# PinJoy.net
KiCad netlist of a schematic drawn in EAGLE
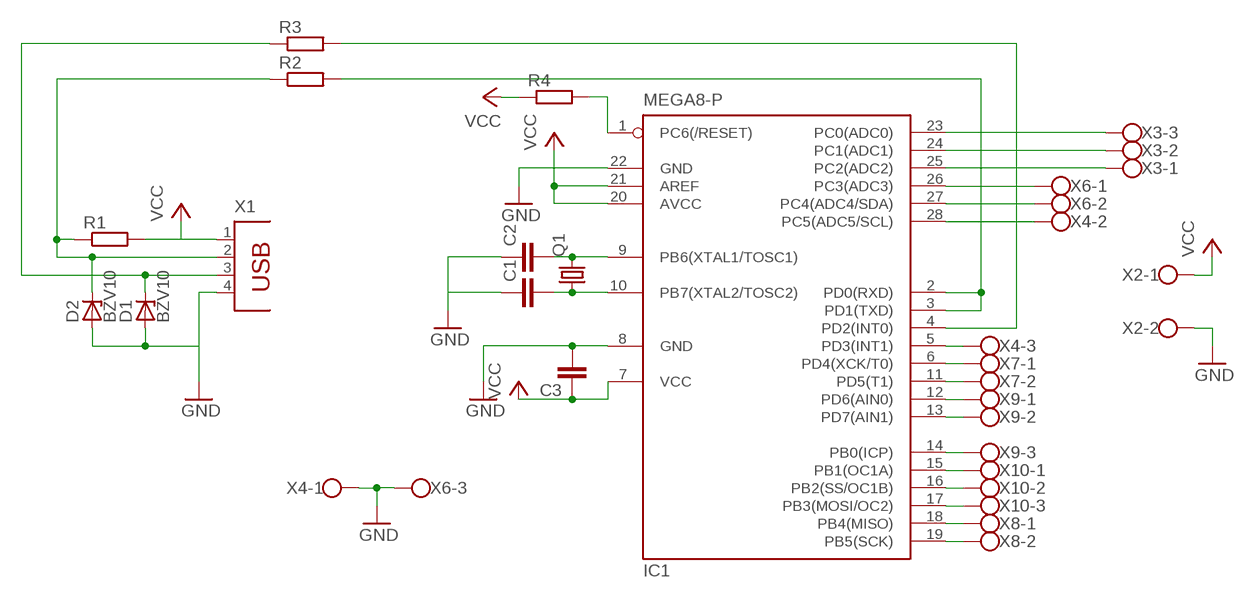
[diagram p0: schematic, sheet 1]

(export (version "E")
  (design (tool "Eeschema 10.0.6"))
  (components
    (comp (ref "C1")
      (value "C-EU025-024X044")
      (footprint "eagle-import:C025-024X044")
      (libsource (lib "eagle-import") (part "C-EU025-024X044"))
    )
    (comp (ref "C2")
      (value "C-EU025-024X044")
      (footprint "eagle-import:C025-024X044")
      (libsource (lib "eagle-import") (part "C-EU025-024X044"))
    )
    (comp (ref "C3")
      (value "C-EU025-024X044")
      (footprint "eagle-import:C025-024X044")
      (libsource (lib "eagle-import") (part "C-EU025-024X044"))
    )
    (comp (ref "D1")
      (value "BZV10")
      (footprint "eagle-import:DO34Z7")
      (libsource (lib "eagle-import") (part "BZV10"))
    )
    (comp (ref "D2")
      (value "BZV10")
      (footprint "eagle-import:DO34Z7")
      (libsource (lib "eagle-import") (part "BZV10"))
    )
    (comp (ref "IC1")
      (value "MEGA8-P")
      (footprint "eagle-import:DIL28-3")
      (libsource (lib "eagle-import") (part "MEGA8-P"))
    )
    (comp (ref "Q1")
      (value "CRYSTALHC18U-V")
      (footprint "eagle-import:HC18U-V")
      (libsource (lib "eagle-import") (part "CRYSTALHC18U-V"))
    )
    (comp (ref "R1")
      (value "R-EU_0204/7")
      (footprint "eagle-import:0204_7")
      (libsource (lib "eagle-import") (part "R-EU_0204/7"))
    )
    (comp (ref "R2")
      (value "R-EU_0204/7")
      (footprint "eagle-import:0204_7")
      (libsource (lib "eagle-import") (part "R-EU_0204/7"))
    )
    (comp (ref "R3")
      (value "R-EU_0204/7")
      (footprint "eagle-import:0204_7")
      (libsource (lib "eagle-import") (part "R-EU_0204/7"))
    )
    (comp (ref "R4")
      (value "R-EU_0204/7")
      (footprint "eagle-import:0204_7")
      (libsource (lib "eagle-import") (part "R-EU_0204/7"))
    )
    (comp (ref "X1")
      (value "PN61729")
      (footprint "eagle-import:PN61729")
      (libsource (lib "eagle-import") (part "PN61729"))
    )
    (comp (ref "X2")
      (value "W237-102")
      (footprint "eagle-import:W237-102")
      (fields (field (name "MPN") "237-102"))
      (libsource (lib "eagle-import") (part "W237-102"))
    )
    (comp (ref "X3")
      (value "W237-103")
      (footprint "eagle-import:W237-103")
      (fields (field (name "MPN") "237-103"))
      (libsource (lib "eagle-import") (part "W237-103"))
    )
    (comp (ref "X4")
      (value "W237-103")
      (footprint "eagle-import:W237-103")
      (fields (field (name "MPN") "237-103"))
      (libsource (lib "eagle-import") (part "W237-103"))
    )
    (comp (ref "X6")
      (value "W237-103")
      (footprint "eagle-import:W237-103")
      (fields (field (name "MPN") "237-103"))
      (libsource (lib "eagle-import") (part "W237-103"))
    )
    (comp (ref "X7")
      (value "W237-102")
      (footprint "eagle-import:W237-102")
      (fields (field (name "MPN") "237-102"))
      (libsource (lib "eagle-import") (part "W237-102"))
    )
    (comp (ref "X8")
      (value "W237-102")
      (footprint "eagle-import:W237-102")
      (fields (field (name "MPN") "237-102"))
      (libsource (lib "eagle-import") (part "W237-102"))
    )
    (comp (ref "X9")
      (value "W237-103")
      (footprint "eagle-import:W237-103")
      (fields (field (name "MPN") "237-103"))
      (libsource (lib "eagle-import") (part "W237-103"))
    )
    (comp (ref "X10")
      (value "W237-103")
      (footprint "eagle-import:W237-103")
      (fields (field (name "MPN") "237-103"))
      (libsource (lib "eagle-import") (part "W237-103"))
    )
  )
  (nets
    (net (code "1") (name "GND") (class "Default")
      (node (ref "C1") (pin "1") (pinfunction "1_1") (pintype "passive"))
      (node (ref "C2") (pin "1") (pinfunction "1_1") (pintype "passive"))
      (node (ref "C3") (pin "2") (pinfunction "2_2") (pintype "passive"))
      (node (ref "D1") (pin "A") (pinfunction "A_A") (pintype "passive"))
      (node (ref "D2") (pin "A") (pinfunction "A_A") (pintype "passive"))
      (node (ref "IC1") (pin "22") (pinfunction "GND_22") (pintype "power_in"))
      (node (ref "IC1") (pin "8") (pinfunction "GND_8") (pintype "power_in"))
      (node (ref "X1") (pin "4") (pinfunction "4_4") (pintype "passive"))
      (node (ref "X2") (pin "2") (pinfunction "KL_2") (pintype "passive"))
      (node (ref "X4") (pin "1") (pinfunction "KL_1") (pintype "passive"))
      (node (ref "X6") (pin "3") (pinfunction "KL_3") (pintype "passive"))
    )
    (net (code "2") (name "Net-(D1-PadC)") (class "Default")
      (node (ref "D1") (pin "C") (pinfunction "C_C") (pintype "passive"))
      (node (ref "R3") (pin "1") (pinfunction "1_1") (pintype "passive"))
      (node (ref "X1") (pin "3") (pinfunction "3_3") (pintype "passive"))
    )
    (net (code "3") (name "Net-(D2-PadC)") (class "Default")
      (node (ref "D2") (pin "C") (pinfunction "C_C") (pintype "passive"))
      (node (ref "R1") (pin "1") (pinfunction "1_1") (pintype "passive"))
      (node (ref "R2") (pin "1") (pinfunction "1_1") (pintype "passive"))
      (node (ref "X1") (pin "2") (pinfunction "2_2") (pintype "passive"))
    )
    (net (code "4") (name "Net-(IC1-PB0(ICP))") (class "Default")
      (node (ref "IC1") (pin "14") (pinfunction "PB0(ICP)_14") (pintype "bidirectional"))
      (node (ref "X9") (pin "3") (pinfunction "KL_3") (pintype "passive"))
    )
    (net (code "5") (name "Net-(IC1-PB1(OC1A))") (class "Default")
      (node (ref "IC1") (pin "15") (pinfunction "PB1(OC1A)_15") (pintype "bidirectional"))
      (node (ref "X10") (pin "1") (pinfunction "KL_1") (pintype "passive"))
    )
    (net (code "6") (name "Net-(IC1-PB2(SS{slash}OC1B))") (class "Default")
      (node (ref "IC1") (pin "16") (pinfunction "PB2(SS/OC1B)_16") (pintype "bidirectional"))
      (node (ref "X10") (pin "2") (pinfunction "KL_2") (pintype "passive"))
    )
    (net (code "7") (name "Net-(IC1-PB3(MOSI{slash}OC2))") (class "Default")
      (node (ref "IC1") (pin "17") (pinfunction "PB3(MOSI/OC2)_17") (pintype "bidirectional"))
      (node (ref "X10") (pin "3") (pinfunction "KL_3") (pintype "passive"))
    )
    (net (code "8") (name "Net-(IC1-PB4(MISO))") (class "Default")
      (node (ref "IC1") (pin "18") (pinfunction "PB4(MISO)_18") (pintype "bidirectional"))
      (node (ref "X8") (pin "1") (pinfunction "KL_1") (pintype "passive"))
    )
    (net (code "9") (name "Net-(IC1-PB5(SCK))") (class "Default")
      (node (ref "IC1") (pin "19") (pinfunction "PB5(SCK)_19") (pintype "bidirectional"))
      (node (ref "X8") (pin "2") (pinfunction "KL_2") (pintype "passive"))
    )
    (net (code "10") (name "Net-(IC1-PB6(XTAL1{slash}TOSC1))") (class "Default")
      (node (ref "C2") (pin "2") (pinfunction "2_2") (pintype "passive"))
      (node (ref "IC1") (pin "9") (pinfunction "PB6(XTAL1/TOSC1)_9") (pintype "bidirectional"))
      (node (ref "Q1") (pin "2") (pinfunction "2_2") (pintype "passive"))
    )
    (net (code "11") (name "Net-(IC1-PB7(XTAL2{slash}TOSC2))") (class "Default")
      (node (ref "C1") (pin "2") (pinfunction "2_2") (pintype "passive"))
      (node (ref "IC1") (pin "10") (pinfunction "PB7(XTAL2/TOSC2)_10") (pintype "bidirectional"))
      (node (ref "Q1") (pin "1") (pinfunction "1_1") (pintype "passive"))
    )
    (net (code "12") (name "Net-(IC1-PC0(ADC0))") (class "Default")
      (node (ref "IC1") (pin "23") (pinfunction "PC0(ADC0)_23") (pintype "bidirectional"))
      (node (ref "X3") (pin "3") (pinfunction "KL_3") (pintype "passive"))
    )
    (net (code "13") (name "Net-(IC1-PC1(ADC1))") (class "Default")
      (node (ref "IC1") (pin "24") (pinfunction "PC1(ADC1)_24") (pintype "bidirectional"))
      (node (ref "X3") (pin "2") (pinfunction "KL_2") (pintype "passive"))
    )
    (net (code "14") (name "Net-(IC1-PC2(ADC2))") (class "Default")
      (node (ref "IC1") (pin "25") (pinfunction "PC2(ADC2)_25") (pintype "bidirectional"))
      (node (ref "X3") (pin "1") (pinfunction "KL_1") (pintype "passive"))
    )
    (net (code "15") (name "Net-(IC1-PC3(ADC3))") (class "Default")
      (node (ref "IC1") (pin "26") (pinfunction "PC3(ADC3)_26") (pintype "bidirectional"))
      (node (ref "X6") (pin "1") (pinfunction "KL_1") (pintype "passive"))
    )
    (net (code "16") (name "Net-(IC1-PC4(ADC4{slash}SDA))") (class "Default")
      (node (ref "IC1") (pin "27") (pinfunction "PC4(ADC4/SDA)_27") (pintype "bidirectional"))
      (node (ref "X6") (pin "2") (pinfunction "KL_2") (pintype "passive"))
    )
    (net (code "17") (name "Net-(IC1-PC5(ADC5{slash}SCL))") (class "Default")
      (node (ref "IC1") (pin "28") (pinfunction "PC5(ADC5/SCL)_28") (pintype "bidirectional"))
      (node (ref "X4") (pin "2") (pinfunction "KL_2") (pintype "passive"))
    )
    (net (code "18") (name "Net-(IC1-PC6({slash}RESET))") (class "Default")
      (node (ref "IC1") (pin "1") (pinfunction "PC6(/RESET)_1") (pintype "bidirectional"))
      (node (ref "R4") (pin "2") (pinfunction "2_2") (pintype "passive"))
    )
    (net (code "19") (name "Net-(IC1-PD0(RXD))") (class "Default")
      (node (ref "IC1") (pin "2") (pinfunction "PD0(RXD)_2") (pintype "bidirectional"))
      (node (ref "IC1") (pin "3") (pinfunction "PD1(TXD)_3") (pintype "bidirectional"))
      (node (ref "R2") (pin "2") (pinfunction "2_2") (pintype "passive"))
    )
    (net (code "20") (name "Net-(IC1-PD2(INT0))") (class "Default")
      (node (ref "IC1") (pin "4") (pinfunction "PD2(INT0)_4") (pintype "bidirectional"))
      (node (ref "R3") (pin "2") (pinfunction "2_2") (pintype "passive"))
    )
    (net (code "21") (name "Net-(IC1-PD3(INT1))") (class "Default")
      (node (ref "IC1") (pin "5") (pinfunction "PD3(INT1)_5") (pintype "bidirectional"))
      (node (ref "X4") (pin "3") (pinfunction "KL_3") (pintype "passive"))
    )
    (net (code "22") (name "Net-(IC1-PD4(XCK{slash}T0))") (class "Default")
      (node (ref "IC1") (pin "6") (pinfunction "PD4(XCK/T0)_6") (pintype "bidirectional"))
      (node (ref "X7") (pin "1") (pinfunction "KL_1") (pintype "passive"))
    )
    (net (code "23") (name "Net-(IC1-PD5(T1))") (class "Default")
      (node (ref "IC1") (pin "11") (pinfunction "PD5(T1)_11") (pintype "bidirectional"))
      (node (ref "X7") (pin "2") (pinfunction "KL_2") (pintype "passive"))
    )
    (net (code "24") (name "Net-(IC1-PD6(AIN0))") (class "Default")
      (node (ref "IC1") (pin "12") (pinfunction "PD6(AIN0)_12") (pintype "bidirectional"))
      (node (ref "X9") (pin "1") (pinfunction "KL_1") (pintype "passive"))
    )
    (net (code "25") (name "Net-(IC1-PD7(AIN1))") (class "Default")
      (node (ref "IC1") (pin "13") (pinfunction "PD7(AIN1)_13") (pintype "bidirectional"))
      (node (ref "X9") (pin "2") (pinfunction "KL_2") (pintype "passive"))
    )
    (net (code "26") (name "VCC") (class "Default")
      (node (ref "C3") (pin "1") (pinfunction "1_1") (pintype "passive"))
      (node (ref "IC1") (pin "20") (pinfunction "AVCC_20") (pintype "power_in"))
      (node (ref "IC1") (pin "21") (pinfunction "AREF_21") (pintype "passive"))
      (node (ref "IC1") (pin "7") (pinfunction "VCC_7") (pintype "power_in"))
      (node (ref "R1") (pin "2") (pinfunction "2_2") (pintype "passive"))
      (node (ref "R4") (pin "1") (pinfunction "1_1") (pintype "passive"))
      (node (ref "X1") (pin "1") (pinfunction "1_1") (pintype "passive"))
      (node (ref "X2") (pin "1") (pinfunction "KL_1") (pintype "passive"))
    )
  )
)
